# ArduinoNorShield.net
KiCad netlist of a schematic drawn in EAGLE
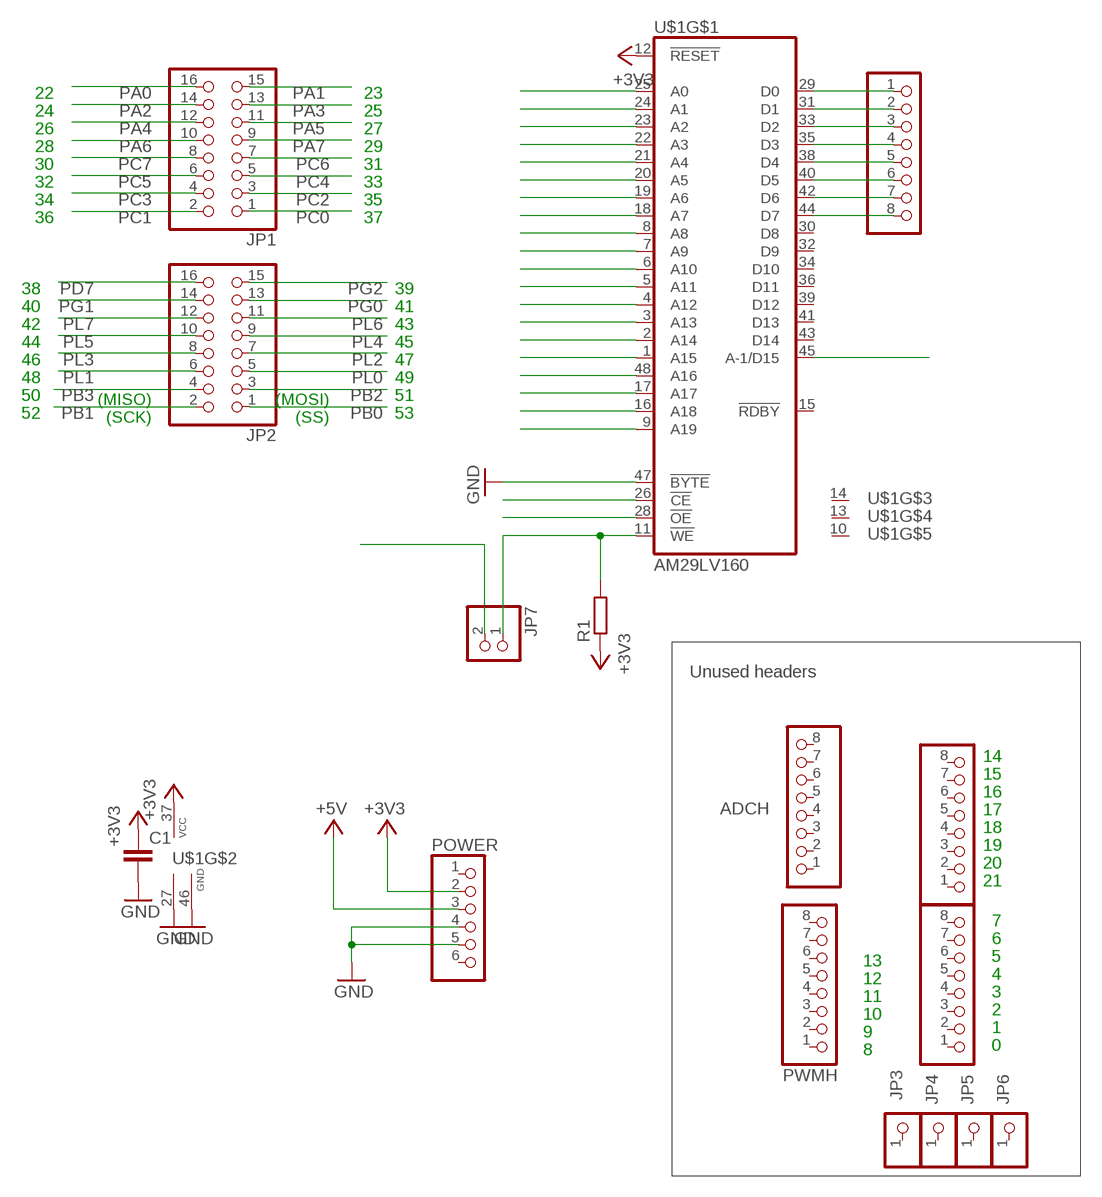
[diagram p0: schematic, sheet 1]

(export (version "E")
  (design (tool "Eeschema 10.0.6"))
  (components
    (comp (ref "ADCH")
      (value "PINHD-1X8")
      (footprint "eagle-import:1X08")
      (libsource (lib "eagle-import") (part "PINHD-1X8"))
    )
    (comp (ref "ADCL")
      (value "PINHD-1X8")
      (footprint "eagle-import:1X08")
      (libsource (lib "eagle-import") (part "PINHD-1X8"))
    )
    (comp (ref "C1")
      (value "C-EUC0805")
      (footprint "eagle-import:C0805")
      (libsource (lib "eagle-import") (part "C-EUC0805"))
    )
    (comp (ref "COMMUNICATION")
      (value "PINHD-1X8")
      (footprint "eagle-import:1X08")
      (libsource (lib "eagle-import") (part "PINHD-1X8"))
    )
    (comp (ref "JP1")
      (value "PINHD-2X8")
      (footprint "eagle-import:2X08")
      (libsource (lib "eagle-import") (part "PINHD-2X8"))
    )
    (comp (ref "JP2")
      (value "PINHD-2X8")
      (footprint "eagle-import:2X08")
      (libsource (lib "eagle-import") (part "PINHD-2X8"))
    )
    (comp (ref "JP3")
      (value "PINHD-1X1")
      (footprint "eagle-import:1X01")
      (libsource (lib "eagle-import") (part "PINHD-1X1"))
    )
    (comp (ref "JP4")
      (value "PINHD-1X1")
      (footprint "eagle-import:1X01")
      (libsource (lib "eagle-import") (part "PINHD-1X1"))
    )
    (comp (ref "JP5")
      (value "PINHD-1X1")
      (footprint "eagle-import:1X01")
      (libsource (lib "eagle-import") (part "PINHD-1X1"))
    )
    (comp (ref "JP6")
      (value "PINHD-1X1")
      (footprint "eagle-import:1X01")
      (libsource (lib "eagle-import") (part "PINHD-1X1"))
    )
    (comp (ref "JP7")
      (value "PINHD-1X2")
      (footprint "eagle-import:1X02")
      (libsource (lib "eagle-import") (part "PINHD-1X2"))
    )
    (comp (ref "POWER")
      (value "PINHD-1X6")
      (footprint "eagle-import:1X06")
      (libsource (lib "eagle-import") (part "PINHD-1X6"))
    )
    (comp (ref "PWMH")
      (value "PINHD-1X8")
      (footprint "eagle-import:1X08")
      (libsource (lib "eagle-import") (part "PINHD-1X8"))
    )
    (comp (ref "PWML")
      (value "PINHD-1X8")
      (footprint "eagle-import:1X08")
      (libsource (lib "eagle-import") (part "PINHD-1X8"))
    )
    (comp (ref "R1")
      (value "R-EU_R0805")
      (footprint "eagle-import:R0805")
      (libsource (lib "eagle-import") (part "R-EU_R0805"))
    )
    (comp (ref "U$1")
      (value "AM29LV160")
      (footprint "eagle-import:TSOP48")
      (libsource (lib "eagle-import") (part "AM29LV160"))
    )
  )
  (nets
    (net (code "1") (name "+3V3") (class "Default")
      (node (ref "C1") (pin "1") (pinfunction "1_1") (pintype "passive"))
      (node (ref "POWER") (pin "2") (pinfunction "2_2") (pintype "passive"))
      (node (ref "R1") (pin "1") (pinfunction "1_1") (pintype "passive"))
      (node (ref "U$1") (pin "12") (pinfunction "~{RESET}_12") (pintype "input"))
      (node (ref "U$1") (pin "37") (pinfunction "VCC_37") (pintype "power_in"))
    )
    (net (code "2") (name "+5V") (class "Default")
      (node (ref "POWER") (pin "3") (pinfunction "3_3") (pintype "passive"))
    )
    (net (code "3") (name "/PA0") (class "Default")
      (node (ref "JP1") (pin "16") (pinfunction "16_16") (pintype "passive"))
      (node (ref "U$1") (pin "45") (pinfunction "A-1/D15_45") (pintype "tri_state"))
    )
    (net (code "4") (name "/PA1") (class "Default")
      (node (ref "JP1") (pin "15") (pinfunction "15_15") (pintype "passive"))
      (node (ref "U$1") (pin "25") (pinfunction "A0_25") (pintype "input"))
    )
    (net (code "5") (name "/PA2") (class "Default")
      (node (ref "JP1") (pin "14") (pinfunction "14_14") (pintype "passive"))
      (node (ref "U$1") (pin "24") (pinfunction "A1_24") (pintype "input"))
    )
    (net (code "6") (name "/PA3") (class "Default")
      (node (ref "JP1") (pin "13") (pinfunction "13_13") (pintype "passive"))
      (node (ref "U$1") (pin "23") (pinfunction "A2_23") (pintype "input"))
    )
    (net (code "7") (name "/PA4") (class "Default")
      (node (ref "JP1") (pin "12") (pinfunction "12_12") (pintype "passive"))
      (node (ref "U$1") (pin "22") (pinfunction "A3_22") (pintype "input"))
    )
    (net (code "8") (name "/PA5") (class "Default")
      (node (ref "JP1") (pin "11") (pinfunction "11_11") (pintype "passive"))
      (node (ref "U$1") (pin "21") (pinfunction "A4_21") (pintype "input"))
    )
    (net (code "9") (name "/PA6") (class "Default")
      (node (ref "JP1") (pin "10") (pinfunction "10_10") (pintype "passive"))
      (node (ref "U$1") (pin "20") (pinfunction "A5_20") (pintype "input"))
    )
    (net (code "10") (name "/PA7") (class "Default")
      (node (ref "JP1") (pin "9") (pinfunction "9_9") (pintype "passive"))
      (node (ref "U$1") (pin "19") (pinfunction "A6_19") (pintype "input"))
    )
    (net (code "11") (name "/PB0") (class "Default")
      (node (ref "JP2") (pin "1") (pinfunction "1_1") (pintype "passive"))
    )
    (net (code "12") (name "/PB1") (class "Default")
      (node (ref "JP2") (pin "2") (pinfunction "2_2") (pintype "passive"))
    )
    (net (code "13") (name "/PB2") (class "Default")
      (node (ref "JP2") (pin "3") (pinfunction "3_3") (pintype "passive"))
    )
    (net (code "14") (name "/PB3") (class "Default")
      (node (ref "JP2") (pin "4") (pinfunction "4_4") (pintype "passive"))
    )
    (net (code "15") (name "/PC0") (class "Default")
      (node (ref "JP1") (pin "1") (pinfunction "1_1") (pintype "passive"))
      (node (ref "U$1") (pin "2") (pinfunction "A14_2") (pintype "input"))
    )
    (net (code "16") (name "/PC1") (class "Default")
      (node (ref "JP1") (pin "2") (pinfunction "2_2") (pintype "passive"))
      (node (ref "U$1") (pin "3") (pinfunction "A13_3") (pintype "input"))
    )
    (net (code "17") (name "/PC2") (class "Default")
      (node (ref "JP1") (pin "3") (pinfunction "3_3") (pintype "passive"))
      (node (ref "U$1") (pin "4") (pinfunction "A12_4") (pintype "input"))
    )
    (net (code "18") (name "/PC3") (class "Default")
      (node (ref "JP1") (pin "4") (pinfunction "4_4") (pintype "passive"))
      (node (ref "U$1") (pin "5") (pinfunction "A11_5") (pintype "input"))
    )
    (net (code "19") (name "/PC4") (class "Default")
      (node (ref "JP1") (pin "5") (pinfunction "5_5") (pintype "passive"))
      (node (ref "U$1") (pin "6") (pinfunction "A10_6") (pintype "input"))
    )
    (net (code "20") (name "/PC5") (class "Default")
      (node (ref "JP1") (pin "6") (pinfunction "6_6") (pintype "passive"))
      (node (ref "U$1") (pin "7") (pinfunction "A9_7") (pintype "input"))
    )
    (net (code "21") (name "/PC6") (class "Default")
      (node (ref "JP1") (pin "7") (pinfunction "7_7") (pintype "passive"))
      (node (ref "U$1") (pin "8") (pinfunction "A8_8") (pintype "input"))
    )
    (net (code "22") (name "/PC7") (class "Default")
      (node (ref "JP1") (pin "8") (pinfunction "8_8") (pintype "passive"))
      (node (ref "U$1") (pin "18") (pinfunction "A7_18") (pintype "input"))
    )
    (net (code "23") (name "/PD7") (class "Default")
      (node (ref "JP2") (pin "16") (pinfunction "16_16") (pintype "passive"))
      (node (ref "U$1") (pin "1") (pinfunction "A15_1") (pintype "input"))
    )
    (net (code "24") (name "/PG0") (class "Default")
      (node (ref "JP2") (pin "13") (pinfunction "13_13") (pintype "passive"))
      (node (ref "U$1") (pin "16") (pinfunction "A18_16") (pintype "input"))
    )
    (net (code "25") (name "/PG1") (class "Default")
      (node (ref "JP2") (pin "14") (pinfunction "14_14") (pintype "passive"))
      (node (ref "U$1") (pin "17") (pinfunction "A17_17") (pintype "input"))
    )
    (net (code "26") (name "/PG2") (class "Default")
      (node (ref "JP2") (pin "15") (pinfunction "15_15") (pintype "passive"))
      (node (ref "U$1") (pin "48") (pinfunction "A16_48") (pintype "input"))
    )
    (net (code "27") (name "/PL0") (class "Default")
      (node (ref "JP2") (pin "5") (pinfunction "5_5") (pintype "passive"))
    )
    (net (code "28") (name "/PL1") (class "Default")
      (node (ref "JP2") (pin "6") (pinfunction "6_6") (pintype "passive"))
    )
    (net (code "29") (name "/PL2") (class "Default")
      (node (ref "JP2") (pin "7") (pinfunction "7_7") (pintype "passive"))
    )
    (net (code "30") (name "/PL3") (class "Default")
      (node (ref "JP2") (pin "8") (pinfunction "8_8") (pintype "passive"))
    )
    (net (code "31") (name "/PL4") (class "Default")
      (node (ref "JP2") (pin "9") (pinfunction "9_9") (pintype "passive"))
      (node (ref "U$1") (pin "28") (pinfunction "~{OE}_28") (pintype "input"))
    )
    (net (code "32") (name "/PL5") (class "Default")
      (node (ref "JP2") (pin "10") (pinfunction "10_10") (pintype "passive"))
      (node (ref "U$1") (pin "26") (pinfunction "~{CE}_26") (pintype "input"))
    )
    (net (code "33") (name "/PL6") (class "Default")
      (node (ref "JP2") (pin "11") (pinfunction "11_11") (pintype "passive"))
      (node (ref "JP7") (pin "2") (pinfunction "2_2") (pintype "passive"))
    )
    (net (code "34") (name "/PL7") (class "Default")
      (node (ref "JP2") (pin "12") (pinfunction "12_12") (pintype "passive"))
      (node (ref "U$1") (pin "9") (pinfunction "A19_9") (pintype "input"))
    )
    (net (code "35") (name "GND") (class "Default")
      (node (ref "C1") (pin "2") (pinfunction "2_2") (pintype "passive"))
      (node (ref "POWER") (pin "4") (pinfunction "4_4") (pintype "passive"))
      (node (ref "POWER") (pin "5") (pinfunction "5_5") (pintype "passive"))
      (node (ref "U$1") (pin "27") (pinfunction "GND_27") (pintype "power_in"))
      (node (ref "U$1") (pin "46") (pinfunction "GND_46") (pintype "power_in"))
      (node (ref "U$1") (pin "47") (pinfunction "~{BYTE}_47") (pintype "input"))
    )
    (net (code "36") (name "Net-(U$1A-D0)") (class "Default")
      (node (ref "ADCL") (pin "1") (pinfunction "1_1") (pintype "passive"))
      (node (ref "U$1") (pin "29") (pinfunction "D0_29") (pintype "tri_state"))
    )
    (net (code "37") (name "Net-(U$1A-D1)") (class "Default")
      (node (ref "ADCL") (pin "2") (pinfunction "2_2") (pintype "passive"))
      (node (ref "U$1") (pin "31") (pinfunction "D1_31") (pintype "tri_state"))
    )
    (net (code "38") (name "Net-(U$1A-D2)") (class "Default")
      (node (ref "ADCL") (pin "3") (pinfunction "3_3") (pintype "passive"))
      (node (ref "U$1") (pin "33") (pinfunction "D2_33") (pintype "tri_state"))
    )
    (net (code "39") (name "Net-(U$1A-D3)") (class "Default")
      (node (ref "ADCL") (pin "4") (pinfunction "4_4") (pintype "passive"))
      (node (ref "U$1") (pin "35") (pinfunction "D3_35") (pintype "tri_state"))
    )
    (net (code "40") (name "Net-(U$1A-D4)") (class "Default")
      (node (ref "ADCL") (pin "5") (pinfunction "5_5") (pintype "passive"))
      (node (ref "U$1") (pin "38") (pinfunction "D4_38") (pintype "tri_state"))
    )
    (net (code "41") (name "Net-(U$1A-D5)") (class "Default")
      (node (ref "ADCL") (pin "6") (pinfunction "6_6") (pintype "passive"))
      (node (ref "U$1") (pin "40") (pinfunction "D5_40") (pintype "tri_state"))
    )
    (net (code "42") (name "Net-(U$1A-D6)") (class "Default")
      (node (ref "ADCL") (pin "7") (pinfunction "7_7") (pintype "passive"))
      (node (ref "U$1") (pin "42") (pinfunction "D6_42") (pintype "tri_state"))
    )
    (net (code "43") (name "Net-(U$1A-D7)") (class "Default")
      (node (ref "ADCL") (pin "8") (pinfunction "8_8") (pintype "passive"))
      (node (ref "U$1") (pin "44") (pinfunction "D7_44") (pintype "tri_state"))
    )
    (net (code "44") (name "Net-(U$1A-~{WE})") (class "Default")
      (node (ref "JP7") (pin "1") (pinfunction "1_1") (pintype "passive"))
      (node (ref "R1") (pin "2") (pinfunction "2_2") (pintype "passive"))
      (node (ref "U$1") (pin "11") (pinfunction "~{WE}_11") (pintype "input"))
    )
    (net (code "45") (name "unconnected-(ADCH-Pad1)") (class "Default")
      (node (ref "ADCH") (pin "1") (pinfunction "1_1") (pintype "passive"))
    )
    (net (code "46") (name "unconnected-(ADCH-Pad2)") (class "Default")
      (node (ref "ADCH") (pin "2") (pinfunction "2_2") (pintype "passive"))
    )
    (net (code "47") (name "unconnected-(ADCH-Pad3)") (class "Default")
      (node (ref "ADCH") (pin "3") (pinfunction "3_3") (pintype "passive"))
    )
    (net (code "48") (name "unconnected-(ADCH-Pad4)") (class "Default")
      (node (ref "ADCH") (pin "4") (pinfunction "4_4") (pintype "passive"))
    )
    (net (code "49") (name "unconnected-(ADCH-Pad5)") (class "Default")
      (node (ref "ADCH") (pin "5") (pinfunction "5_5") (pintype "passive"))
    )
    (net (code "50") (name "unconnected-(ADCH-Pad6)") (class "Default")
      (node (ref "ADCH") (pin "6") (pinfunction "6_6") (pintype "passive"))
    )
    (net (code "51") (name "unconnected-(ADCH-Pad7)") (class "Default")
      (node (ref "ADCH") (pin "7") (pinfunction "7_7") (pintype "passive"))
    )
    (net (code "52") (name "unconnected-(ADCH-Pad8)") (class "Default")
      (node (ref "ADCH") (pin "8") (pinfunction "8_8") (pintype "passive"))
    )
    (net (code "53") (name "unconnected-(COMMUNICATION-Pad1)") (class "Default")
      (node (ref "COMMUNICATION") (pin "1") (pinfunction "1_1") (pintype "passive"))
    )
    (net (code "54") (name "unconnected-(COMMUNICATION-Pad2)") (class "Default")
      (node (ref "COMMUNICATION") (pin "2") (pinfunction "2_2") (pintype "passive"))
    )
    (net (code "55") (name "unconnected-(COMMUNICATION-Pad3)") (class "Default")
      (node (ref "COMMUNICATION") (pin "3") (pinfunction "3_3") (pintype "passive"))
    )
    (net (code "56") (name "unconnected-(COMMUNICATION-Pad4)") (class "Default")
      (node (ref "COMMUNICATION") (pin "4") (pinfunction "4_4") (pintype "passive"))
    )
    (net (code "57") (name "unconnected-(COMMUNICATION-Pad5)") (class "Default")
      (node (ref "COMMUNICATION") (pin "5") (pinfunction "5_5") (pintype "passive"))
    )
    (net (code "58") (name "unconnected-(COMMUNICATION-Pad6)") (class "Default")
      (node (ref "COMMUNICATION") (pin "6") (pinfunction "6_6") (pintype "passive"))
    )
    (net (code "59") (name "unconnected-(COMMUNICATION-Pad7)") (class "Default")
      (node (ref "COMMUNICATION") (pin "7") (pinfunction "7_7") (pintype "passive"))
    )
    (net (code "60") (name "unconnected-(COMMUNICATION-Pad8)") (class "Default")
      (node (ref "COMMUNICATION") (pin "8") (pinfunction "8_8") (pintype "passive"))
    )
    (net (code "61") (name "unconnected-(JP3-Pad1)") (class "Default")
      (node (ref "JP3") (pin "1") (pinfunction "1_1") (pintype "passive"))
    )
    (net (code "62") (name "unconnected-(JP4-Pad1)") (class "Default")
      (node (ref "JP4") (pin "1") (pinfunction "1_1") (pintype "passive"))
    )
    (net (code "63") (name "unconnected-(JP5-Pad1)") (class "Default")
      (node (ref "JP5") (pin "1") (pinfunction "1_1") (pintype "passive"))
    )
    (net (code "64") (name "unconnected-(JP6-Pad1)") (class "Default")
      (node (ref "JP6") (pin "1") (pinfunction "1_1") (pintype "passive"))
    )
    (net (code "65") (name "unconnected-(POWER-Pad1)") (class "Default")
      (node (ref "POWER") (pin "1") (pinfunction "1_1") (pintype "passive"))
    )
    (net (code "66") (name "unconnected-(POWER-Pad6)") (class "Default")
      (node (ref "POWER") (pin "6") (pinfunction "6_6") (pintype "passive"))
    )
    (net (code "67") (name "unconnected-(PWMH-Pad1)") (class "Default")
      (node (ref "PWMH") (pin "1") (pinfunction "1_1") (pintype "passive"))
    )
    (net (code "68") (name "unconnected-(PWMH-Pad2)") (class "Default")
      (node (ref "PWMH") (pin "2") (pinfunction "2_2") (pintype "passive"))
    )
    (net (code "69") (name "unconnected-(PWMH-Pad3)") (class "Default")
      (node (ref "PWMH") (pin "3") (pinfunction "3_3") (pintype "passive"))
    )
    (net (code "70") (name "unconnected-(PWMH-Pad4)") (class "Default")
      (node (ref "PWMH") (pin "4") (pinfunction "4_4") (pintype "passive"))
    )
    (net (code "71") (name "unconnected-(PWMH-Pad5)") (class "Default")
      (node (ref "PWMH") (pin "5") (pinfunction "5_5") (pintype "passive"))
    )
    (net (code "72") (name "unconnected-(PWMH-Pad6)") (class "Default")
      (node (ref "PWMH") (pin "6") (pinfunction "6_6") (pintype "passive"))
    )
    (net (code "73") (name "unconnected-(PWMH-Pad7)") (class "Default")
      (node (ref "PWMH") (pin "7") (pinfunction "7_7") (pintype "passive"))
    )
    (net (code "74") (name "unconnected-(PWMH-Pad8)") (class "Default")
      (node (ref "PWMH") (pin "8") (pinfunction "8_8") (pintype "passive"))
    )
    (net (code "75") (name "unconnected-(PWML-Pad1)") (class "Default")
      (node (ref "PWML") (pin "1") (pinfunction "1_1") (pintype "passive"))
    )
    (net (code "76") (name "unconnected-(PWML-Pad2)") (class "Default")
      (node (ref "PWML") (pin "2") (pinfunction "2_2") (pintype "passive"))
    )
    (net (code "77") (name "unconnected-(PWML-Pad3)") (class "Default")
      (node (ref "PWML") (pin "3") (pinfunction "3_3") (pintype "passive"))
    )
    (net (code "78") (name "unconnected-(PWML-Pad4)") (class "Default")
      (node (ref "PWML") (pin "4") (pinfunction "4_4") (pintype "passive"))
    )
    (net (code "79") (name "unconnected-(PWML-Pad5)") (class "Default")
      (node (ref "PWML") (pin "5") (pinfunction "5_5") (pintype "passive"))
    )
    (net (code "80") (name "unconnected-(PWML-Pad6)") (class "Default")
      (node (ref "PWML") (pin "6") (pinfunction "6_6") (pintype "passive"))
    )
    (net (code "81") (name "unconnected-(PWML-Pad7)") (class "Default")
      (node (ref "PWML") (pin "7") (pinfunction "7_7") (pintype "passive"))
    )
    (net (code "82") (name "unconnected-(PWML-Pad8)") (class "Default")
      (node (ref "PWML") (pin "8") (pinfunction "8_8") (pintype "passive"))
    )
    (net (code "83") (name "unconnected-(U$1A-D8-Pad30)") (class "Default")
      (node (ref "U$1") (pin "30") (pinfunction "D8_30") (pintype "tri_state"))
    )
    (net (code "84") (name "unconnected-(U$1A-D9-Pad32)") (class "Default")
      (node (ref "U$1") (pin "32") (pinfunction "D9_32") (pintype "tri_state"))
    )
    (net (code "85") (name "unconnected-(U$1A-D10-Pad34)") (class "Default")
      (node (ref "U$1") (pin "34") (pinfunction "D10_34") (pintype "tri_state"))
    )
    (net (code "86") (name "unconnected-(U$1A-D11-Pad36)") (class "Default")
      (node (ref "U$1") (pin "36") (pinfunction "D11_36") (pintype "tri_state"))
    )
    (net (code "87") (name "unconnected-(U$1A-D12-Pad39)") (class "Default")
      (node (ref "U$1") (pin "39") (pinfunction "D12_39") (pintype "tri_state"))
    )
    (net (code "88") (name "unconnected-(U$1A-D13-Pad41)") (class "Default")
      (node (ref "U$1") (pin "41") (pinfunction "D13_41") (pintype "tri_state"))
    )
    (net (code "89") (name "unconnected-(U$1A-D14-Pad43)") (class "Default")
      (node (ref "U$1") (pin "43") (pinfunction "D14_43") (pintype "tri_state"))
    )
    (net (code "90") (name "unconnected-(U$1A-~{RDBY}-Pad15)") (class "Default")
      (node (ref "U$1") (pin "15") (pinfunction "~{RDBY}_15") (pintype "output"))
    )
    (net (code "91") (name "unconnected-(U$1C-NC-Pad14)") (class "Default")
      (node (ref "U$1") (pin "14") (pinfunction "NC_14") (pintype "no_connect"))
    )
    (net (code "92") (name "unconnected-(U$1D-NC-Pad13)") (class "Default")
      (node (ref "U$1") (pin "13") (pinfunction "NC_13") (pintype "no_connect"))
    )
    (net (code "93") (name "unconnected-(U$1E-NC-Pad10)") (class "Default")
      (node (ref "U$1") (pin "10") (pinfunction "NC_10") (pintype "no_connect"))
    )
  )
)
